# Top.net
KiCad netlist of a schematic drawn in Altium Designer
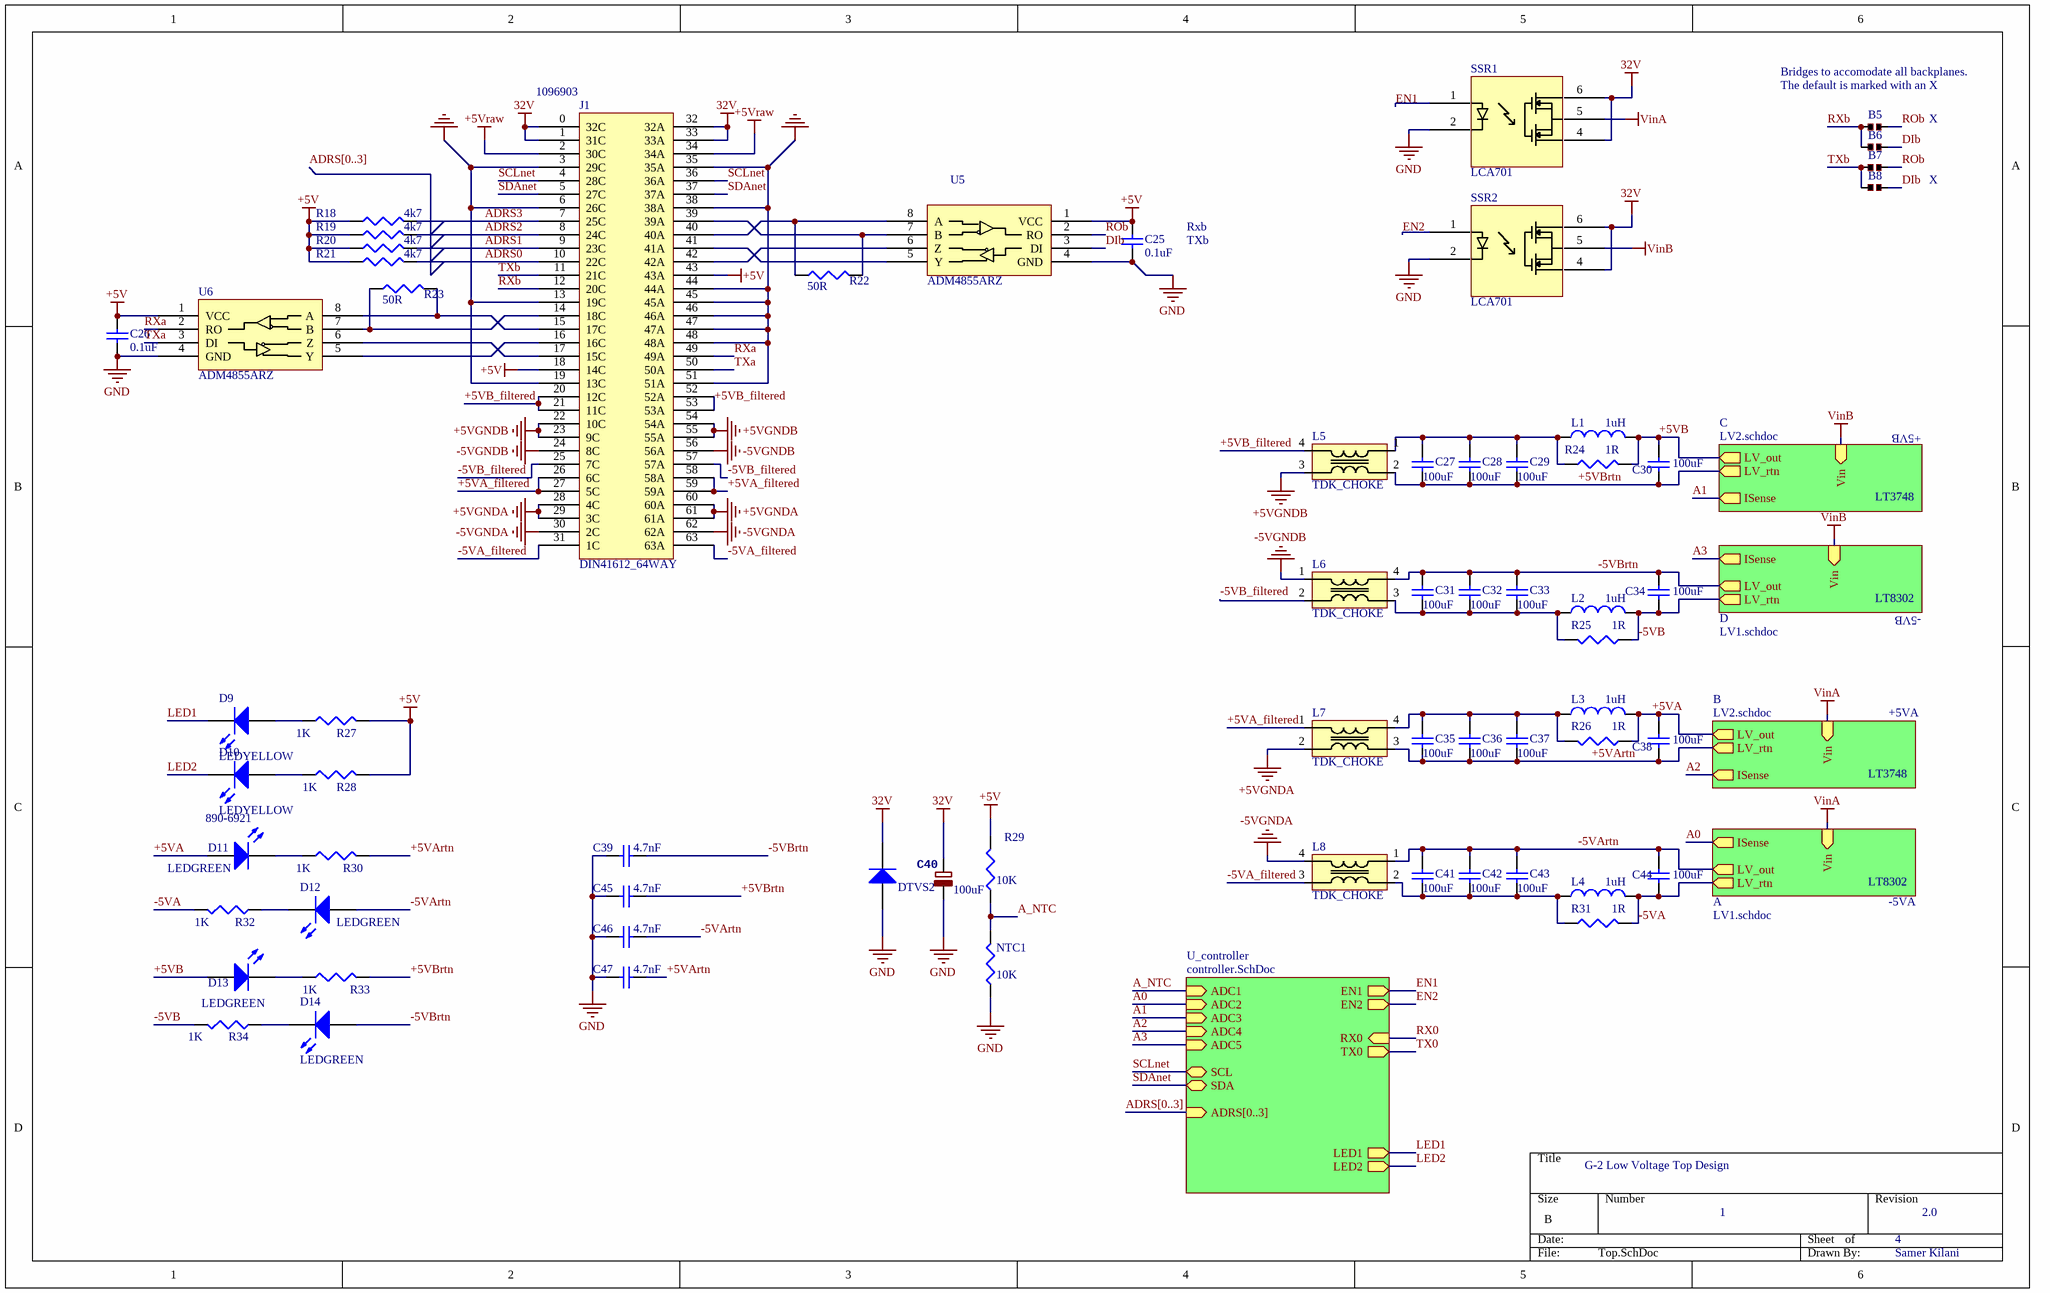
[diagram p0: Top.SchDoc]

(export (version "E")
  (design (tool "Eeschema 10.0.6"))
  (components
    (comp (ref "B5") (value "Bridge") (footprint "Bridge") (libsource (lib "G2_LV") (part "Bridge")))
    (comp (ref "B6") (value "Bridge") (footprint "Bridge") (libsource (lib "G2_LV") (part "Bridge")))
    (comp (ref "B7") (value "Bridge") (footprint "Bridge") (libsource (lib "G2_LV") (part "Bridge")))
    (comp (ref "B8") (value "Bridge") (footprint "Bridge") (libsource (lib "G2_LV") (part "Bridge")))
    (comp (ref "C25")
      (value "0.1uF")
      (footprint "1608[0603]")
      (description "Capacitor (Semiconductor SIM Model)")
      (fields
        (field (name "PARTNO") "CC0603KRX7R9BB104")
        (field (name "Comment") "Cap Semi")
        (field (name "PUBLISHER") "Altium Limited")
      )
      (libsource (lib "Miscellaneous Devices") (part "Cap Semi"))
    )
    (comp (ref "C26")
      (value "0.1uF")
      (footprint "1608[0603]")
      (description "Capacitor (Semiconductor SIM Model)")
      (fields
        (field (name "PARTNO") "CC0603KRX7R9BB104")
        (field (name "Comment") "Cap Semi")
        (field (name "PUBLISHER") "Altium Limited")
      )
      (libsource (lib "Miscellaneous Devices") (part "Cap Semi"))
    )
    (comp (ref "C27")
      (value "100uF")
      (footprint "C1210")
      (description "Capacitor (Semiconductor SIM Model)")
      (fields
        (field (name "PARTNO") "CL32A107MPVNNNE")
        (field (name "Comment") "Cap Semi")
        (field (name "PUBLISHER") "Altium Limited")
      )
      (libsource (lib "Miscellaneous Devices") (part "Cap Semi"))
    )
    (comp (ref "C28")
      (value "100uF")
      (footprint "C1210")
      (description "Capacitor (Semiconductor SIM Model)")
      (fields
        (field (name "PARTNO") "CL32A107MPVNNNE")
        (field (name "Comment") "Cap Semi")
        (field (name "PUBLISHER") "Altium Limited")
      )
      (libsource (lib "Miscellaneous Devices") (part "Cap Semi"))
    )
    (comp (ref "C29")
      (value "100uF")
      (footprint "C1210")
      (description "Capacitor (Semiconductor SIM Model)")
      (fields
        (field (name "PARTNO") "CL32A107MPVNNNE")
        (field (name "Comment") "Cap Semi")
        (field (name "PUBLISHER") "Altium Limited")
      )
      (libsource (lib "Miscellaneous Devices") (part "Cap Semi"))
    )
    (comp (ref "C30")
      (value "100uF")
      (footprint "C1210")
      (description "Capacitor (Semiconductor SIM Model)")
      (fields
        (field (name "PARTNO") "C3225X5R0J107M250AC")
        (field (name "Comment") "Cap Semi")
        (field (name "PUBLISHER") "Altium Limited")
      )
      (libsource (lib "Miscellaneous Devices") (part "Cap Semi"))
    )
    (comp (ref "C31")
      (value "100uF")
      (footprint "C1210")
      (description "Capacitor (Semiconductor SIM Model)")
      (fields
        (field (name "PARTNO") "CL32A107MPVNNNE")
        (field (name "Comment") "Cap Semi")
        (field (name "PUBLISHER") "Altium Limited")
      )
      (libsource (lib "Miscellaneous Devices") (part "Cap Semi"))
    )
    (comp (ref "C32")
      (value "100uF")
      (footprint "C1210")
      (description "Capacitor (Semiconductor SIM Model)")
      (fields
        (field (name "PARTNO") "CL32A107MPVNNNE")
        (field (name "Comment") "Cap Semi")
        (field (name "PUBLISHER") "Altium Limited")
      )
      (libsource (lib "Miscellaneous Devices") (part "Cap Semi"))
    )
    (comp (ref "C33")
      (value "100uF")
      (footprint "C1210")
      (description "Capacitor (Semiconductor SIM Model)")
      (fields
        (field (name "PARTNO") "CL32A107MPVNNNE")
        (field (name "Comment") "Cap Semi")
        (field (name "PUBLISHER") "Altium Limited")
      )
      (libsource (lib "Miscellaneous Devices") (part "Cap Semi"))
    )
    (comp (ref "C34")
      (value "100uF")
      (footprint "C1210")
      (description "Capacitor (Semiconductor SIM Model)")
      (fields
        (field (name "PARTNO") "C3225X5R0J107M250AC")
        (field (name "Comment") "Cap Semi")
        (field (name "PUBLISHER") "Altium Limited")
      )
      (libsource (lib "Miscellaneous Devices") (part "Cap Semi"))
    )
    (comp (ref "C35")
      (value "100uF")
      (footprint "C1210")
      (description "Capacitor (Semiconductor SIM Model)")
      (fields
        (field (name "PARTNO") "CL32A107MPVNNNE")
        (field (name "Comment") "Cap Semi")
        (field (name "PUBLISHER") "Altium Limited")
      )
      (libsource (lib "Miscellaneous Devices") (part "Cap Semi"))
    )
    (comp (ref "C36")
      (value "100uF")
      (footprint "C1210")
      (description "Capacitor (Semiconductor SIM Model)")
      (fields
        (field (name "PARTNO") "CL32A107MPVNNNE")
        (field (name "Comment") "Cap Semi")
        (field (name "PUBLISHER") "Altium Limited")
      )
      (libsource (lib "Miscellaneous Devices") (part "Cap Semi"))
    )
    (comp (ref "C37")
      (value "100uF")
      (footprint "C1210")
      (description "Capacitor (Semiconductor SIM Model)")
      (fields
        (field (name "PARTNO") "CL32A107MPVNNNE")
        (field (name "Comment") "Cap Semi")
        (field (name "PUBLISHER") "Altium Limited")
      )
      (libsource (lib "Miscellaneous Devices") (part "Cap Semi"))
    )
    (comp (ref "C38")
      (value "100uF")
      (footprint "C1210")
      (description "Capacitor (Semiconductor SIM Model)")
      (fields
        (field (name "PARTNO") "C3225X5R0J107M250AC")
        (field (name "Comment") "Cap Semi")
        (field (name "PUBLISHER") "Altium Limited")
      )
      (libsource (lib "Miscellaneous Devices") (part "Cap Semi"))
    )
    (comp (ref "C39")
      (value "4.7nF")
      (footprint "1812")
      (description "Capacitor (Semiconductor SIM Model)")
      (fields
        (field (name "PARTNO") "C1812C472KDRACTU")
        (field (name "Comment") "Cap Semi")
        (field (name "PUBLISHER") "Altium Limited")
      )
      (libsource (lib "G2_LV") (part "Cap Semi"))
    )
    (comp (ref "C40")
      (value "100uF")
      (footprint "EMVY101ARA101MKE0S")
      (fields (field (name "PARTNO") "EMVY101ARA101MKE0S"))
      (libsource (lib "G2_LV") (part "CPOL-EUD"))
    )
    (comp (ref "C41")
      (value "100uF")
      (footprint "C1210")
      (description "Capacitor (Semiconductor SIM Model)")
      (fields
        (field (name "PARTNO") "CL32A107MPVNNNE")
        (field (name "Comment") "Cap Semi")
        (field (name "PUBLISHER") "Altium Limited")
      )
      (libsource (lib "Miscellaneous Devices") (part "Cap Semi"))
    )
    (comp (ref "C42")
      (value "100uF")
      (footprint "C1210")
      (description "Capacitor (Semiconductor SIM Model)")
      (fields
        (field (name "PARTNO") "CL32A107MPVNNNE")
        (field (name "Comment") "Cap Semi")
        (field (name "PUBLISHER") "Altium Limited")
      )
      (libsource (lib "Miscellaneous Devices") (part "Cap Semi"))
    )
    (comp (ref "C43")
      (value "100uF")
      (footprint "C1210")
      (description "Capacitor (Semiconductor SIM Model)")
      (fields
        (field (name "PARTNO") "CL32A107MPVNNNE")
        (field (name "Comment") "Cap Semi")
        (field (name "PUBLISHER") "Altium Limited")
      )
      (libsource (lib "Miscellaneous Devices") (part "Cap Semi"))
    )
    (comp (ref "C44")
      (value "100uF")
      (footprint "C1210")
      (description "Capacitor (Semiconductor SIM Model)")
      (fields
        (field (name "PARTNO") "C3225X5R0J107M250AC")
        (field (name "Comment") "Cap Semi")
        (field (name "PUBLISHER") "Altium Limited")
      )
      (libsource (lib "Miscellaneous Devices") (part "Cap Semi"))
    )
    (comp (ref "C45")
      (value "4.7nF")
      (footprint "1812")
      (description "Capacitor (Semiconductor SIM Model)")
      (fields
        (field (name "PARTNO") "C1812C472KDRACTU")
        (field (name "Comment") "Cap Semi")
        (field (name "PUBLISHER") "Altium Limited")
      )
      (libsource (lib "G2_LV") (part "Cap Semi"))
    )
    (comp (ref "C46")
      (value "4.7nF")
      (footprint "1812")
      (description "Capacitor (Semiconductor SIM Model)")
      (fields
        (field (name "PARTNO") "C1812C472KDRACTU")
        (field (name "Comment") "Cap Semi")
        (field (name "PUBLISHER") "Altium Limited")
      )
      (libsource (lib "G2_LV") (part "Cap Semi"))
    )
    (comp (ref "C47")
      (value "4.7nF")
      (footprint "1812")
      (description "Capacitor (Semiconductor SIM Model)")
      (fields
        (field (name "PARTNO") "C1812C472KDRACTU")
        (field (name "Comment") "Cap Semi")
        (field (name "PUBLISHER") "Altium Limited")
      )
      (libsource (lib "G2_LV") (part "Cap Semi"))
    )
    (comp (ref "D9")
      (value "LEDYELLOW")
      (footprint "LEDYELLOW")
      (fields (field (name "PARTNO") "550-0307F"))
      (libsource (lib "G2_LV") (part "LEDYELLOW"))
    )
    (comp (ref "D10")
      (value "LEDYELLOW")
      (footprint "LEDYELLOW")
      (fields (field (name "PARTNO") "550-0307F"))
      (libsource (lib "G2_LV") (part "LEDYELLOW"))
    )
    (comp (ref "D11")
      (value "LEDGREEN")
      (footprint "LEDGREEN")
      (fields (field (name "PARTNO") "550-0207F") (field (name "SUPPLIER PART NUMBER 1") "890-6921"))
      (libsource (lib "G2_LV") (part "LEDGREEN"))
    )
    (comp (ref "D12")
      (value "LEDGREEN")
      (footprint "LEDGREEN")
      (fields (field (name "PARTNO") "550-0207F"))
      (libsource (lib "G2_LV") (part "LEDGREEN"))
    )
    (comp (ref "D13")
      (value "LEDGREEN")
      (footprint "LEDGREEN")
      (fields (field (name "PARTNO") "550-0207F"))
      (libsource (lib "G2_LV") (part "LEDGREEN"))
    )
    (comp (ref "D14")
      (value "LEDGREEN")
      (footprint "LEDGREEN")
      (fields (field (name "PARTNO") "550-0207F"))
      (libsource (lib "G2_LV") (part "LEDGREEN"))
    )
    (comp (ref "DTVS2")
      (value "SMBJ48A")
      (footprint "SMBJ")
      (description "TVS")
      (fields (field (name "PARTNO") "SMBJ36A") (field (name "PUBLISHER") "Altium Limited"))
      (libsource (lib "G2_LV") (part "SMBJ"))
    )
    (comp (ref "J1")
      (value "DIN41612_64WAY")
      (footprint "09 03 164 6919")
      (fields (field (name "PARTNO") "0903 164 6921") (field (name "SUPPLIER PART NUMBER 1") "1096903"))
      (libsource (lib "G2_LV") (part "DIN41612_64WAY"))
    )
    (comp (ref "L1")
      (value "1uH")
      (footprint "MPLC0730")
      (description "Inductor")
      (fields (field (name "PARTNO") "MPLC0730L1R0") (field (name "PUBLISHER") "Altium Limited"))
      (libsource (lib "G2_LV") (part "Inductor"))
    )
    (comp (ref "L2")
      (value "1uH")
      (footprint "MPLC0730")
      (description "Inductor")
      (fields (field (name "PARTNO") "MPLC0730L1R0") (field (name "PUBLISHER") "Altium Limited"))
      (libsource (lib "G2_LV") (part "Inductor"))
    )
    (comp (ref "L3")
      (value "1uH")
      (footprint "MPLC0730")
      (description "Inductor")
      (fields (field (name "PARTNO") "MPLC0730L1R0") (field (name "PUBLISHER") "Altium Limited"))
      (libsource (lib "G2_LV") (part "Inductor"))
    )
    (comp (ref "L4")
      (value "1uH")
      (footprint "MPLC0730")
      (description "Inductor")
      (fields (field (name "PARTNO") "MPLC0730L1R0") (field (name "PUBLISHER") "Altium Limited"))
      (libsource (lib "G2_LV") (part "Inductor"))
    )
    (comp (ref "L5")
      (value "TDK_CHOKE")
      (footprint "ACMV_TDK")
      (fields (field (name "PARTNO") "ACM90V-701-2PL"))
      (libsource (lib "") (part "TDK_CHOKE_1"))
    )
    (comp (ref "L6")
      (value "TDK_CHOKE")
      (footprint "ACMV_TDK")
      (fields (field (name "PARTNO") "ACM90V-701-2PL"))
      (libsource (lib "G2_LV") (part "TDK_CHOKE"))
    )
    (comp (ref "L7")
      (value "TDK_CHOKE")
      (footprint "ACMV_TDK")
      (fields (field (name "PARTNO") "ACM90V-701-2PL"))
      (libsource (lib "G2_LV") (part "TDK_CHOKE"))
    )
    (comp (ref "L8")
      (value "TDK_CHOKE")
      (footprint "ACMV_TDK")
      (fields (field (name "PARTNO") "ACM90V-701-2PL"))
      (libsource (lib "") (part "TDK_CHOKE_1"))
    )
    (comp (ref "NTC1")
      (value "10K")
      (footprint "J1-0603")
      (description "Resistor")
      (fields (field (name "PARTNO") "NCP18XH103J03RB") (field (name "PUBLISHER") "Altium Limited"))
      (libsource (lib "Miscellaneous Devices") (part "Res3"))
    )
    (comp (ref "R18")
      (value "4k7")
      (footprint "J1-0603")
      (description "Resistor")
      (fields (field (name "Comment") "Res3") (field (name "PUBLISHER") "Altium Limited"))
      (libsource (lib "Miscellaneous Devices") (part "Res3"))
    )
    (comp (ref "R19")
      (value "4k7")
      (footprint "J1-0603")
      (description "Resistor")
      (fields (field (name "Comment") "Res3") (field (name "PUBLISHER") "Altium Limited"))
      (libsource (lib "Miscellaneous Devices") (part "Res3"))
    )
    (comp (ref "R20")
      (value "4k7")
      (footprint "J1-0603")
      (description "Resistor")
      (fields (field (name "Comment") "Res3") (field (name "PUBLISHER") "Altium Limited"))
      (libsource (lib "Miscellaneous Devices") (part "Res3"))
    )
    (comp (ref "R21")
      (value "4k7")
      (footprint "J1-0603")
      (description "Resistor")
      (fields (field (name "Comment") "Res3") (field (name "PUBLISHER") "Altium Limited"))
      (libsource (lib "Miscellaneous Devices") (part "Res3"))
    )
    (comp (ref "R22")
      (value "50R")
      (footprint "J1-0603")
      (description "Resistor")
      (fields (field (name "PUBLISHER") "Altium Limited"))
      (libsource (lib "Miscellaneous Devices") (part "Res3"))
    )
    (comp (ref "R23")
      (value "50R")
      (footprint "J1-0603")
      (description "Resistor")
      (fields (field (name "PUBLISHER") "Altium Limited"))
      (libsource (lib "Miscellaneous Devices") (part "Res3"))
    )
    (comp (ref "R24")
      (value "1R")
      (footprint "J1-0603")
      (description "Resistor")
      (fields (field (name "Comment") "Res3") (field (name "PUBLISHER") "Altium Limited"))
      (libsource (lib "Miscellaneous Devices") (part "Res3"))
    )
    (comp (ref "R25")
      (value "1R")
      (footprint "J1-0603")
      (description "Resistor")
      (fields (field (name "Comment") "Res3") (field (name "PUBLISHER") "Altium Limited"))
      (libsource (lib "Miscellaneous Devices") (part "Res3"))
    )
    (comp (ref "R26")
      (value "1R")
      (footprint "J1-0603")
      (description "Resistor")
      (fields (field (name "Comment") "Res3") (field (name "PUBLISHER") "Altium Limited"))
      (libsource (lib "Miscellaneous Devices") (part "Res3"))
    )
    (comp (ref "R27")
      (value "1K")
      (footprint "J1-0603")
      (description "Resistor")
      (fields (field (name "Comment") "Res3") (field (name "PUBLISHER") "Altium Limited"))
      (libsource (lib "Miscellaneous Devices") (part "Res3"))
    )
    (comp (ref "R28")
      (value "1K")
      (footprint "J1-0603")
      (description "Resistor")
      (fields (field (name "Comment") "Res3") (field (name "PUBLISHER") "Altium Limited"))
      (libsource (lib "Miscellaneous Devices") (part "Res3"))
    )
    (comp (ref "R29")
      (value "10K")
      (footprint "J1-0603")
      (description "Resistor")
      (fields (field (name "PUBLISHER") "Altium Limited"))
      (libsource (lib "Miscellaneous Devices") (part "Res3"))
    )
    (comp (ref "R30")
      (value "1K")
      (footprint "J1-0603")
      (description "Resistor")
      (fields (field (name "Comment") "Res3") (field (name "PUBLISHER") "Altium Limited"))
      (libsource (lib "Miscellaneous Devices") (part "Res3"))
    )
    (comp (ref "R31")
      (value "1R")
      (footprint "J1-0603")
      (description "Resistor")
      (fields (field (name "Comment") "Res3") (field (name "PUBLISHER") "Altium Limited"))
      (libsource (lib "Miscellaneous Devices") (part "Res3"))
    )
    (comp (ref "R32")
      (value "1K")
      (footprint "J1-0603")
      (description "Resistor")
      (fields (field (name "Comment") "Res3") (field (name "PUBLISHER") "Altium Limited"))
      (libsource (lib "Miscellaneous Devices") (part "Res3"))
    )
    (comp (ref "R33")
      (value "1K")
      (footprint "J1-0603")
      (description "Resistor")
      (fields (field (name "Comment") "Res3") (field (name "PUBLISHER") "Altium Limited"))
      (libsource (lib "Miscellaneous Devices") (part "Res3"))
    )
    (comp (ref "R34")
      (value "1K")
      (footprint "J1-0603")
      (description "Resistor")
      (fields (field (name "Comment") "Res3") (field (name "PUBLISHER") "Altium Limited"))
      (libsource (lib "Miscellaneous Devices") (part "Res3"))
    )
    (comp (ref "SSR1")
      (value "LCA701")
      (footprint "LCA701S")
      (fields (field (name "PARTNO") "LCA701S"))
      (libsource (lib "G2_LV") (part "LCA701"))
    )
    (comp (ref "SSR2")
      (value "LCA701")
      (footprint "LCA701S")
      (fields (field (name "PARTNO") "LCA701S"))
      (libsource (lib "G2_LV") (part "LCA701"))
    )
    (comp (ref "U5")
      (value "ADM4855ARZ")
      (footprint "SOICN8")
      (libsource (lib "BACKPLANElib") (part "SP3084EEN-L"))
    )
    (comp (ref "U6") (value "ADM4855ARZ") (footprint "SOICN8") (libsource (lib "") (part "SP3084EEN-L_1")))
  )
  (nets
    (net (code "1") (name "+5V") (class "Default")
      (node (ref "C25") (pin "2") (pinfunction "2_2") (pintype "passive"))
      (node (ref "C26") (pin "2") (pinfunction "2_2") (pintype "passive"))
      (node (ref "J1") (pin "18") (pinfunction "14C_18") (pintype "passive"))
      (node (ref "J1") (pin "43") (pinfunction "43A_43") (pintype "passive"))
      (node (ref "R18") (pin "1") (pinfunction "1_1") (pintype "passive"))
      (node (ref "R19") (pin "1") (pinfunction "1_1") (pintype "passive"))
      (node (ref "R20") (pin "1") (pinfunction "1_1") (pintype "passive"))
      (node (ref "R21") (pin "1") (pinfunction "1_1") (pintype "passive"))
      (node (ref "R27") (pin "2") (pinfunction "2_2") (pintype "passive"))
      (node (ref "R28") (pin "2") (pinfunction "2_2") (pintype "passive"))
      (node (ref "R29") (pin "2") (pinfunction "2_2") (pintype "passive"))
      (node (ref "U5") (pin "1") (pinfunction "VCC_1") (pintype "passive"))
      (node (ref "U6") (pin "1") (pinfunction "VCC_1") (pintype "passive"))
    )
    (net (code "2") (name "+5VGNDA") (class "Default")
      (node (ref "J1") (pin "28") (pinfunction "4C_28") (pintype "passive"))
      (node (ref "J1") (pin "29") (pinfunction "3C_29") (pintype "passive"))
      (node (ref "J1") (pin "60") (pinfunction "60A_60") (pintype "passive"))
      (node (ref "J1") (pin "61") (pinfunction "61A_61") (pintype "passive"))
      (node (ref "L7") (pin "2") (pinfunction "2_2") (pintype "passive"))
    )
    (net (code "3") (name "+5VGNDB") (class "Default")
      (node (ref "J1") (pin "22") (pinfunction "10C_22") (pintype "passive"))
      (node (ref "J1") (pin "23") (pinfunction "9C_23") (pintype "passive"))
      (node (ref "J1") (pin "54") (pinfunction "54A_54") (pintype "passive"))
      (node (ref "J1") (pin "55") (pinfunction "55A_55") (pintype "passive"))
      (node (ref "L5") (pin "3") (pinfunction "3_3") (pintype "passive"))
    )
    (net (code "4") (name "+5Vraw") (class "Default")
      (node (ref "J1") (pin "2") (pinfunction "30C_2") (pintype "passive"))
      (node (ref "J1") (pin "34") (pinfunction "34A_34") (pintype "passive"))
    )
    (net (code "5") (name "-5VGNDA") (class "Default")
      (node (ref "J1") (pin "30") (pinfunction "2C_30") (pintype "passive"))
      (node (ref "J1") (pin "62") (pinfunction "62A_62") (pintype "passive"))
      (node (ref "L8") (pin "4") (pinfunction "4_4") (pintype "passive"))
    )
    (net (code "6") (name "-5VGNDB") (class "Default")
      (node (ref "J1") (pin "24") (pinfunction "8C_24") (pintype "passive"))
      (node (ref "J1") (pin "56") (pinfunction "56A_56") (pintype "passive"))
      (node (ref "L6") (pin "1") (pinfunction "1_1") (pintype "passive"))
    )
    (net (code "7") (name "/+5VA") (class "Default")
      (node (ref "C38") (pin "1") (pinfunction "1_1") (pintype "passive"))
      (node (ref "D11") (pin "2") (pinfunction "A_2") (pintype "passive"))
      (node (ref "L3") (pin "2") (pinfunction "2_2") (pintype "passive"))
      (node (ref "R26") (pin "1") (pinfunction "1_1") (pintype "passive"))
    )
    (net (code "8") (name "/+5VA_filtered") (class "Default")
      (node (ref "J1") (pin "26") (pinfunction "6C_26") (pintype "passive"))
      (node (ref "J1") (pin "27") (pinfunction "5C_27") (pintype "passive"))
      (node (ref "J1") (pin "58") (pinfunction "58A_58") (pintype "passive"))
      (node (ref "J1") (pin "59") (pinfunction "59A_59") (pintype "passive"))
      (node (ref "L7") (pin "1") (pinfunction "1_1") (pintype "passive"))
    )
    (net (code "9") (name "/+5VArtn") (class "Default")
      (node (ref "C35") (pin "2") (pinfunction "2_2") (pintype "passive"))
      (node (ref "C36") (pin "2") (pinfunction "2_2") (pintype "passive"))
      (node (ref "C37") (pin "2") (pinfunction "2_2") (pintype "passive"))
      (node (ref "C38") (pin "2") (pinfunction "2_2") (pintype "passive"))
      (node (ref "C47") (pin "2") (pinfunction "2_2") (pintype "passive"))
      (node (ref "L7") (pin "3") (pinfunction "3_3") (pintype "passive"))
      (node (ref "R30") (pin "2") (pinfunction "2_2") (pintype "passive"))
    )
    (net (code "10") (name "/+5VB") (class "Default")
      (node (ref "C30") (pin "2") (pinfunction "2_2") (pintype "passive"))
      (node (ref "D13") (pin "2") (pinfunction "A_2") (pintype "passive"))
      (node (ref "L1") (pin "2") (pinfunction "2_2") (pintype "passive"))
      (node (ref "R24") (pin "2") (pinfunction "2_2") (pintype "passive"))
    )
    (net (code "11") (name "/+5VB_filtered") (class "Default")
      (node (ref "J1") (pin "20") (pinfunction "12C_20") (pintype "passive"))
      (node (ref "J1") (pin "21") (pinfunction "11C_21") (pintype "passive"))
      (node (ref "J1") (pin "52") (pinfunction "52A_52") (pintype "passive"))
      (node (ref "J1") (pin "53") (pinfunction "53A_53") (pintype "passive"))
      (node (ref "L5") (pin "4") (pinfunction "4_4") (pintype "passive"))
    )
    (net (code "12") (name "/+5VBrtn") (class "Default")
      (node (ref "C27") (pin "1") (pinfunction "1_1") (pintype "passive"))
      (node (ref "C28") (pin "1") (pinfunction "1_1") (pintype "passive"))
      (node (ref "C29") (pin "1") (pinfunction "1_1") (pintype "passive"))
      (node (ref "C30") (pin "1") (pinfunction "1_1") (pintype "passive"))
      (node (ref "C45") (pin "2") (pinfunction "2_2") (pintype "passive"))
      (node (ref "L5") (pin "2") (pinfunction "2_2") (pintype "passive"))
      (node (ref "R33") (pin "2") (pinfunction "2_2") (pintype "passive"))
    )
    (net (code "13") (name "/-5VA") (class "Default")
      (node (ref "C44") (pin "1") (pinfunction "1_1") (pintype "passive"))
      (node (ref "L4") (pin "2") (pinfunction "2_2") (pintype "passive"))
      (node (ref "R31") (pin "2") (pinfunction "2_2") (pintype "passive"))
      (node (ref "R32") (pin "2") (pinfunction "2_2") (pintype "passive"))
    )
    (net (code "14") (name "/-5VA_filtered") (class "Default")
      (node (ref "J1") (pin "31") (pinfunction "1C_31") (pintype "passive"))
      (node (ref "J1") (pin "63") (pinfunction "63A_63") (pintype "passive"))
      (node (ref "L8") (pin "3") (pinfunction "3_3") (pintype "passive"))
    )
    (net (code "15") (name "/-5VArtn") (class "Default")
      (node (ref "C41") (pin "2") (pinfunction "2_2") (pintype "passive"))
      (node (ref "C42") (pin "2") (pinfunction "2_2") (pintype "passive"))
      (node (ref "C43") (pin "2") (pinfunction "2_2") (pintype "passive"))
      (node (ref "C44") (pin "2") (pinfunction "2_2") (pintype "passive"))
      (node (ref "C46") (pin "2") (pinfunction "2_2") (pintype "passive"))
      (node (ref "D12") (pin "2") (pinfunction "A_2") (pintype "passive"))
      (node (ref "L8") (pin "1") (pinfunction "1_1") (pintype "passive"))
    )
    (net (code "16") (name "/-5VB") (class "Default")
      (node (ref "C34") (pin "2") (pinfunction "2_2") (pintype "passive"))
      (node (ref "L2") (pin "2") (pinfunction "2_2") (pintype "passive"))
      (node (ref "R25") (pin "1") (pinfunction "1_1") (pintype "passive"))
      (node (ref "R34") (pin "2") (pinfunction "2_2") (pintype "passive"))
    )
    (net (code "17") (name "/-5VB_filtered") (class "Default")
      (node (ref "J1") (pin "25") (pinfunction "7C_25") (pintype "passive"))
      (node (ref "J1") (pin "57") (pinfunction "57A_57") (pintype "passive"))
      (node (ref "L6") (pin "2") (pinfunction "2_2") (pintype "passive"))
    )
    (net (code "18") (name "/-5VBrtn") (class "Default")
      (node (ref "C31") (pin "1") (pinfunction "1_1") (pintype "passive"))
      (node (ref "C32") (pin "1") (pinfunction "1_1") (pintype "passive"))
      (node (ref "C33") (pin "1") (pinfunction "1_1") (pintype "passive"))
      (node (ref "C34") (pin "1") (pinfunction "1_1") (pintype "passive"))
      (node (ref "C39") (pin "2") (pinfunction "2_2") (pintype "passive"))
      (node (ref "D14") (pin "2") (pinfunction "A_2") (pintype "passive"))
      (node (ref "L6") (pin "4") (pinfunction "4_4") (pintype "passive"))
    )
    (net (code "23") (name "/ADRS0") (class "Default")
      (node (ref "J1") (pin "10") (pinfunction "22C_10") (pintype "passive"))
      (node (ref "R21") (pin "2") (pinfunction "2_2") (pintype "passive"))
    )
    (net (code "24") (name "/ADRS1") (class "Default")
      (node (ref "J1") (pin "9") (pinfunction "23C_9") (pintype "passive"))
      (node (ref "R20") (pin "2") (pinfunction "2_2") (pintype "passive"))
    )
    (net (code "25") (name "/ADRS2") (class "Default")
      (node (ref "J1") (pin "8") (pinfunction "24C_8") (pintype "passive"))
      (node (ref "R19") (pin "2") (pinfunction "2_2") (pintype "passive"))
    )
    (net (code "26") (name "/ADRS3") (class "Default")
      (node (ref "J1") (pin "7") (pinfunction "25C_7") (pintype "passive"))
      (node (ref "R18") (pin "2") (pinfunction "2_2") (pintype "passive"))
    )
    (net (code "28") (name "/A_NTC") (class "Default")
      (node (ref "NTC1") (pin "2") (pinfunction "2_2") (pintype "passive"))
      (node (ref "R29") (pin "1") (pinfunction "1_1") (pintype "passive"))
    )
    (net (code "29") (name "/DIb") (class "Default")
      (node (ref "B6") (pin "2") (pinfunction "2_2") (pintype "passive"))
      (node (ref "B8") (pin "2") (pinfunction "2_2") (pintype "passive"))
      (node (ref "U5") (pin "3") (pinfunction "DI_3") (pintype "passive"))
    )
    (net (code "30") (name "/EN1") (class "Default")
      (node (ref "SSR1") (pin "1") (pinfunction "1_1") (pintype "passive"))
    )
    (net (code "31") (name "/EN2") (class "Default")
      (node (ref "SSR2") (pin "1") (pinfunction "1_1") (pintype "passive"))
    )
    (net (code "32") (name "/LED1") (class "Default")
      (node (ref "D9") (pin "1") (pinfunction "K_1") (pintype "passive"))
    )
    (net (code "33") (name "/LED2") (class "Default")
      (node (ref "D10") (pin "1") (pinfunction "K_1") (pintype "passive"))
    )
    (net (code "34") (name "/ROb") (class "Default")
      (node (ref "B5") (pin "2") (pinfunction "2_2") (pintype "passive"))
      (node (ref "B7") (pin "2") (pinfunction "2_2") (pintype "passive"))
      (node (ref "U5") (pin "2") (pinfunction "RO_2") (pintype "passive"))
    )
    (net (code "36") (name "/RXa") (class "Default")
      (node (ref "J1") (pin "49") (pinfunction "49A_49") (pintype "passive"))
      (node (ref "U6") (pin "2") (pinfunction "RO_2") (pintype "passive"))
    )
    (net (code "37") (name "/RXb") (class "Default")
      (node (ref "B5") (pin "1") (pinfunction "1_1") (pintype "passive"))
      (node (ref "B6") (pin "1") (pinfunction "1_1") (pintype "passive"))
      (node (ref "J1") (pin "12") (pinfunction "20C_12") (pintype "passive"))
    )
    (net (code "38") (name "/SCLnet") (class "Default")
      (node (ref "J1") (pin "36") (pinfunction "36A_36") (pintype "passive"))
      (node (ref "J1") (pin "4") (pinfunction "28C_4") (pintype "passive"))
    )
    (net (code "39") (name "/SDAnet") (class "Default")
      (node (ref "J1") (pin "37") (pinfunction "37A_37") (pintype "passive"))
      (node (ref "J1") (pin "5") (pinfunction "27C_5") (pintype "passive"))
    )
    (net (code "41") (name "/TXa") (class "Default")
      (node (ref "J1") (pin "50") (pinfunction "50A_50") (pintype "passive"))
      (node (ref "U6") (pin "3") (pinfunction "DI_3") (pintype "passive"))
    )
    (net (code "42") (name "/TXb") (class "Default")
      (node (ref "B7") (pin "1") (pinfunction "1_1") (pintype "passive"))
      (node (ref "B8") (pin "1") (pinfunction "1_1") (pintype "passive"))
      (node (ref "J1") (pin "11") (pinfunction "21C_11") (pintype "passive"))
    )
    (net (code "43") (name "32V") (class "Default")
      (node (ref "C40") (pin "1") (pinfunction "1_1") (pintype "passive"))
      (node (ref "DTVS2") (pin "1") (pinfunction "K_1") (pintype "passive"))
      (node (ref "J1") (pin "0") (pinfunction "32C_0") (pintype "passive"))
      (node (ref "J1") (pin "1") (pinfunction "31C_1") (pintype "passive"))
      (node (ref "J1") (pin "32") (pinfunction "32A_32") (pintype "passive"))
      (node (ref "J1") (pin "33") (pinfunction "33A_33") (pintype "passive"))
      (node (ref "SSR1") (pin "4") (pinfunction "4_4") (pintype "passive"))
      (node (ref "SSR1") (pin "6") (pinfunction "6_6") (pintype "passive"))
      (node (ref "SSR2") (pin "4") (pinfunction "4_4") (pintype "passive"))
      (node (ref "SSR2") (pin "6") (pinfunction "6_6") (pintype "passive"))
    )
    (net (code "44") (name "GND") (class "Default")
      (node (ref "C25") (pin "1") (pinfunction "1_1") (pintype "passive"))
      (node (ref "C26") (pin "1") (pinfunction "1_1") (pintype "passive"))
      (node (ref "C39") (pin "1") (pinfunction "1_1") (pintype "passive"))
      (node (ref "C40") (pin "2") (pinfunction "2_2") (pintype "passive"))
      (node (ref "C45") (pin "1") (pinfunction "1_1") (pintype "passive"))
      (node (ref "C46") (pin "1") (pinfunction "1_1") (pintype "passive"))
      (node (ref "C47") (pin "1") (pinfunction "1_1") (pintype "passive"))
      (node (ref "DTVS2") (pin "2") (pinfunction "A_2") (pintype "passive"))
      (node (ref "J1") (pin "13") (pinfunction "19C_13") (pintype "passive"))
      (node (ref "J1") (pin "19") (pinfunction "13C_19") (pintype "passive"))
      (node (ref "J1") (pin "3") (pinfunction "29C_3") (pintype "passive"))
      (node (ref "J1") (pin "35") (pinfunction "35A_35") (pintype "passive"))
      (node (ref "J1") (pin "38") (pinfunction "38A_38") (pintype "passive"))
      (node (ref "J1") (pin "44") (pinfunction "44A_44") (pintype "passive"))
      (node (ref "J1") (pin "45") (pinfunction "45A_45") (pintype "passive"))
      (node (ref "J1") (pin "46") (pinfunction "46A_46") (pintype "passive"))
      (node (ref "J1") (pin "47") (pinfunction "47A_47") (pintype "passive"))
      (node (ref "J1") (pin "48") (pinfunction "48A_48") (pintype "passive"))
      (node (ref "J1") (pin "51") (pinfunction "51A_51") (pintype "passive"))
      (node (ref "J1") (pin "6") (pinfunction "26C_6") (pintype "passive"))
      (node (ref "NTC1") (pin "1") (pinfunction "1_1") (pintype "passive"))
      (node (ref "SSR1") (pin "2") (pinfunction "2_2") (pintype "passive"))
      (node (ref "SSR2") (pin "2") (pinfunction "2_2") (pintype "passive"))
      (node (ref "U5") (pin "4") (pinfunction "GND_4") (pintype "passive"))
      (node (ref "U6") (pin "4") (pinfunction "GND_4") (pintype "passive"))
    )
    (net (code "45") (name "Net-(C27-Pad2)") (class "Default")
      (node (ref "C27") (pin "2") (pinfunction "2_2") (pintype "passive"))
      (node (ref "C28") (pin "2") (pinfunction "2_2") (pintype "passive"))
      (node (ref "C29") (pin "2") (pinfunction "2_2") (pintype "passive"))
      (node (ref "L1") (pin "1") (pinfunction "1_1") (pintype "passive"))
      (node (ref "L5") (pin "1") (pinfunction "1_1") (pintype "passive"))
      (node (ref "R24") (pin "1") (pinfunction "1_1") (pintype "passive"))
    )
    (net (code "46") (name "Net-(C31-Pad2)") (class "Default")
      (node (ref "C31") (pin "2") (pinfunction "2_2") (pintype "passive"))
      (node (ref "C32") (pin "2") (pinfunction "2_2") (pintype "passive"))
      (node (ref "C33") (pin "2") (pinfunction "2_2") (pintype "passive"))
      (node (ref "L2") (pin "1") (pinfunction "1_1") (pintype "passive"))
      (node (ref "L6") (pin "3") (pinfunction "3_3") (pintype "passive"))
      (node (ref "R25") (pin "2") (pinfunction "2_2") (pintype "passive"))
    )
    (net (code "47") (name "Net-(C35-Pad1)") (class "Default")
      (node (ref "C35") (pin "1") (pinfunction "1_1") (pintype "passive"))
      (node (ref "C36") (pin "1") (pinfunction "1_1") (pintype "passive"))
      (node (ref "C37") (pin "1") (pinfunction "1_1") (pintype "passive"))
      (node (ref "L3") (pin "1") (pinfunction "1_1") (pintype "passive"))
      (node (ref "L7") (pin "4") (pinfunction "4_4") (pintype "passive"))
      (node (ref "R26") (pin "2") (pinfunction "2_2") (pintype "passive"))
    )
    (net (code "48") (name "Net-(C41-Pad1)") (class "Default")
      (node (ref "C41") (pin "1") (pinfunction "1_1") (pintype "passive"))
      (node (ref "C42") (pin "1") (pinfunction "1_1") (pintype "passive"))
      (node (ref "C43") (pin "1") (pinfunction "1_1") (pintype "passive"))
      (node (ref "L4") (pin "1") (pinfunction "1_1") (pintype "passive"))
      (node (ref "L8") (pin "2") (pinfunction "2_2") (pintype "passive"))
      (node (ref "R31") (pin "1") (pinfunction "1_1") (pintype "passive"))
    )
    (net (code "49") (name "Net-(D9-A)") (class "Default")
      (node (ref "D9") (pin "2") (pinfunction "A_2") (pintype "passive"))
      (node (ref "R27") (pin "1") (pinfunction "1_1") (pintype "passive"))
    )
    (net (code "50") (name "Net-(D10-A)") (class "Default")
      (node (ref "D10") (pin "2") (pinfunction "A_2") (pintype "passive"))
      (node (ref "R28") (pin "1") (pinfunction "1_1") (pintype "passive"))
    )
    (net (code "51") (name "Net-(D11-K)") (class "Default")
      (node (ref "D11") (pin "1") (pinfunction "K_1") (pintype "passive"))
      (node (ref "R30") (pin "1") (pinfunction "1_1") (pintype "passive"))
    )
    (net (code "52") (name "Net-(D12-K)") (class "Default")
      (node (ref "D12") (pin "1") (pinfunction "K_1") (pintype "passive"))
      (node (ref "R32") (pin "1") (pinfunction "1_1") (pintype "passive"))
    )
    (net (code "53") (name "Net-(D13-K)") (class "Default")
      (node (ref "D13") (pin "1") (pinfunction "K_1") (pintype "passive"))
      (node (ref "R33") (pin "1") (pinfunction "1_1") (pintype "passive"))
    )
    (net (code "54") (name "Net-(D14-K)") (class "Default")
      (node (ref "D14") (pin "1") (pinfunction "K_1") (pintype "passive"))
      (node (ref "R34") (pin "1") (pinfunction "1_1") (pintype "passive"))
    )
    (net (code "55") (name "Net-(J1-15C)") (class "Default")
      (node (ref "J1") (pin "17") (pinfunction "15C_17") (pintype "passive"))
      (node (ref "U6") (pin "6") (pinfunction "Z_6") (pintype "passive"))
    )
    (net (code "56") (name "Net-(J1-16C)") (class "Default")
      (node (ref "J1") (pin "16") (pinfunction "16C_16") (pintype "passive"))
      (node (ref "U6") (pin "5") (pinfunction "Y_5") (pintype "passive"))
    )
    (net (code "57") (name "Net-(J1-17C)") (class "Default")
      (node (ref "J1") (pin "15") (pinfunction "17C_15") (pintype "passive"))
      (node (ref "R23") (pin "2") (pinfunction "2_2") (pintype "passive"))
      (node (ref "U6") (pin "8") (pinfunction "A_8") (pintype "passive"))
    )
    (net (code "58") (name "Net-(J1-18C)") (class "Default")
      (node (ref "J1") (pin "14") (pinfunction "18C_14") (pintype "passive"))
      (node (ref "R23") (pin "1") (pinfunction "1_1") (pintype "passive"))
      (node (ref "U6") (pin "7") (pinfunction "B_7") (pintype "passive"))
    )
    (net (code "59") (name "Net-(J1-39A)") (class "Default")
      (node (ref "J1") (pin "39") (pinfunction "39A_39") (pintype "passive"))
      (node (ref "R22") (pin "2") (pinfunction "2_2") (pintype "passive"))
      (node (ref "U5") (pin "7") (pinfunction "B_7") (pintype "passive"))
    )
    (net (code "60") (name "Net-(J1-40A)") (class "Default")
      (node (ref "J1") (pin "40") (pinfunction "40A_40") (pintype "passive"))
      (node (ref "R22") (pin "1") (pinfunction "1_1") (pintype "passive"))
      (node (ref "U5") (pin "8") (pinfunction "A_8") (pintype "passive"))
    )
    (net (code "61") (name "Net-(J1-41A)") (class "Default")
      (node (ref "J1") (pin "41") (pinfunction "41A_41") (pintype "passive"))
      (node (ref "U5") (pin "5") (pinfunction "Y_5") (pintype "passive"))
    )
    (net (code "62") (name "Net-(J1-42A)") (class "Default")
      (node (ref "J1") (pin "42") (pinfunction "42A_42") (pintype "passive"))
      (node (ref "U5") (pin "6") (pinfunction "Z_6") (pintype "passive"))
    )
    (net (code "63") (name "VinA") (class "Default")
      (node (ref "SSR1") (pin "5") (pinfunction "5_5") (pintype "passive"))
    )
    (net (code "64") (name "VinB") (class "Default")
      (node (ref "SSR2") (pin "5") (pinfunction "5_5") (pintype "passive"))
    )
  )
)
